# 4G_Modem.net
KiCad netlist of a schematic drawn in Altium Designer
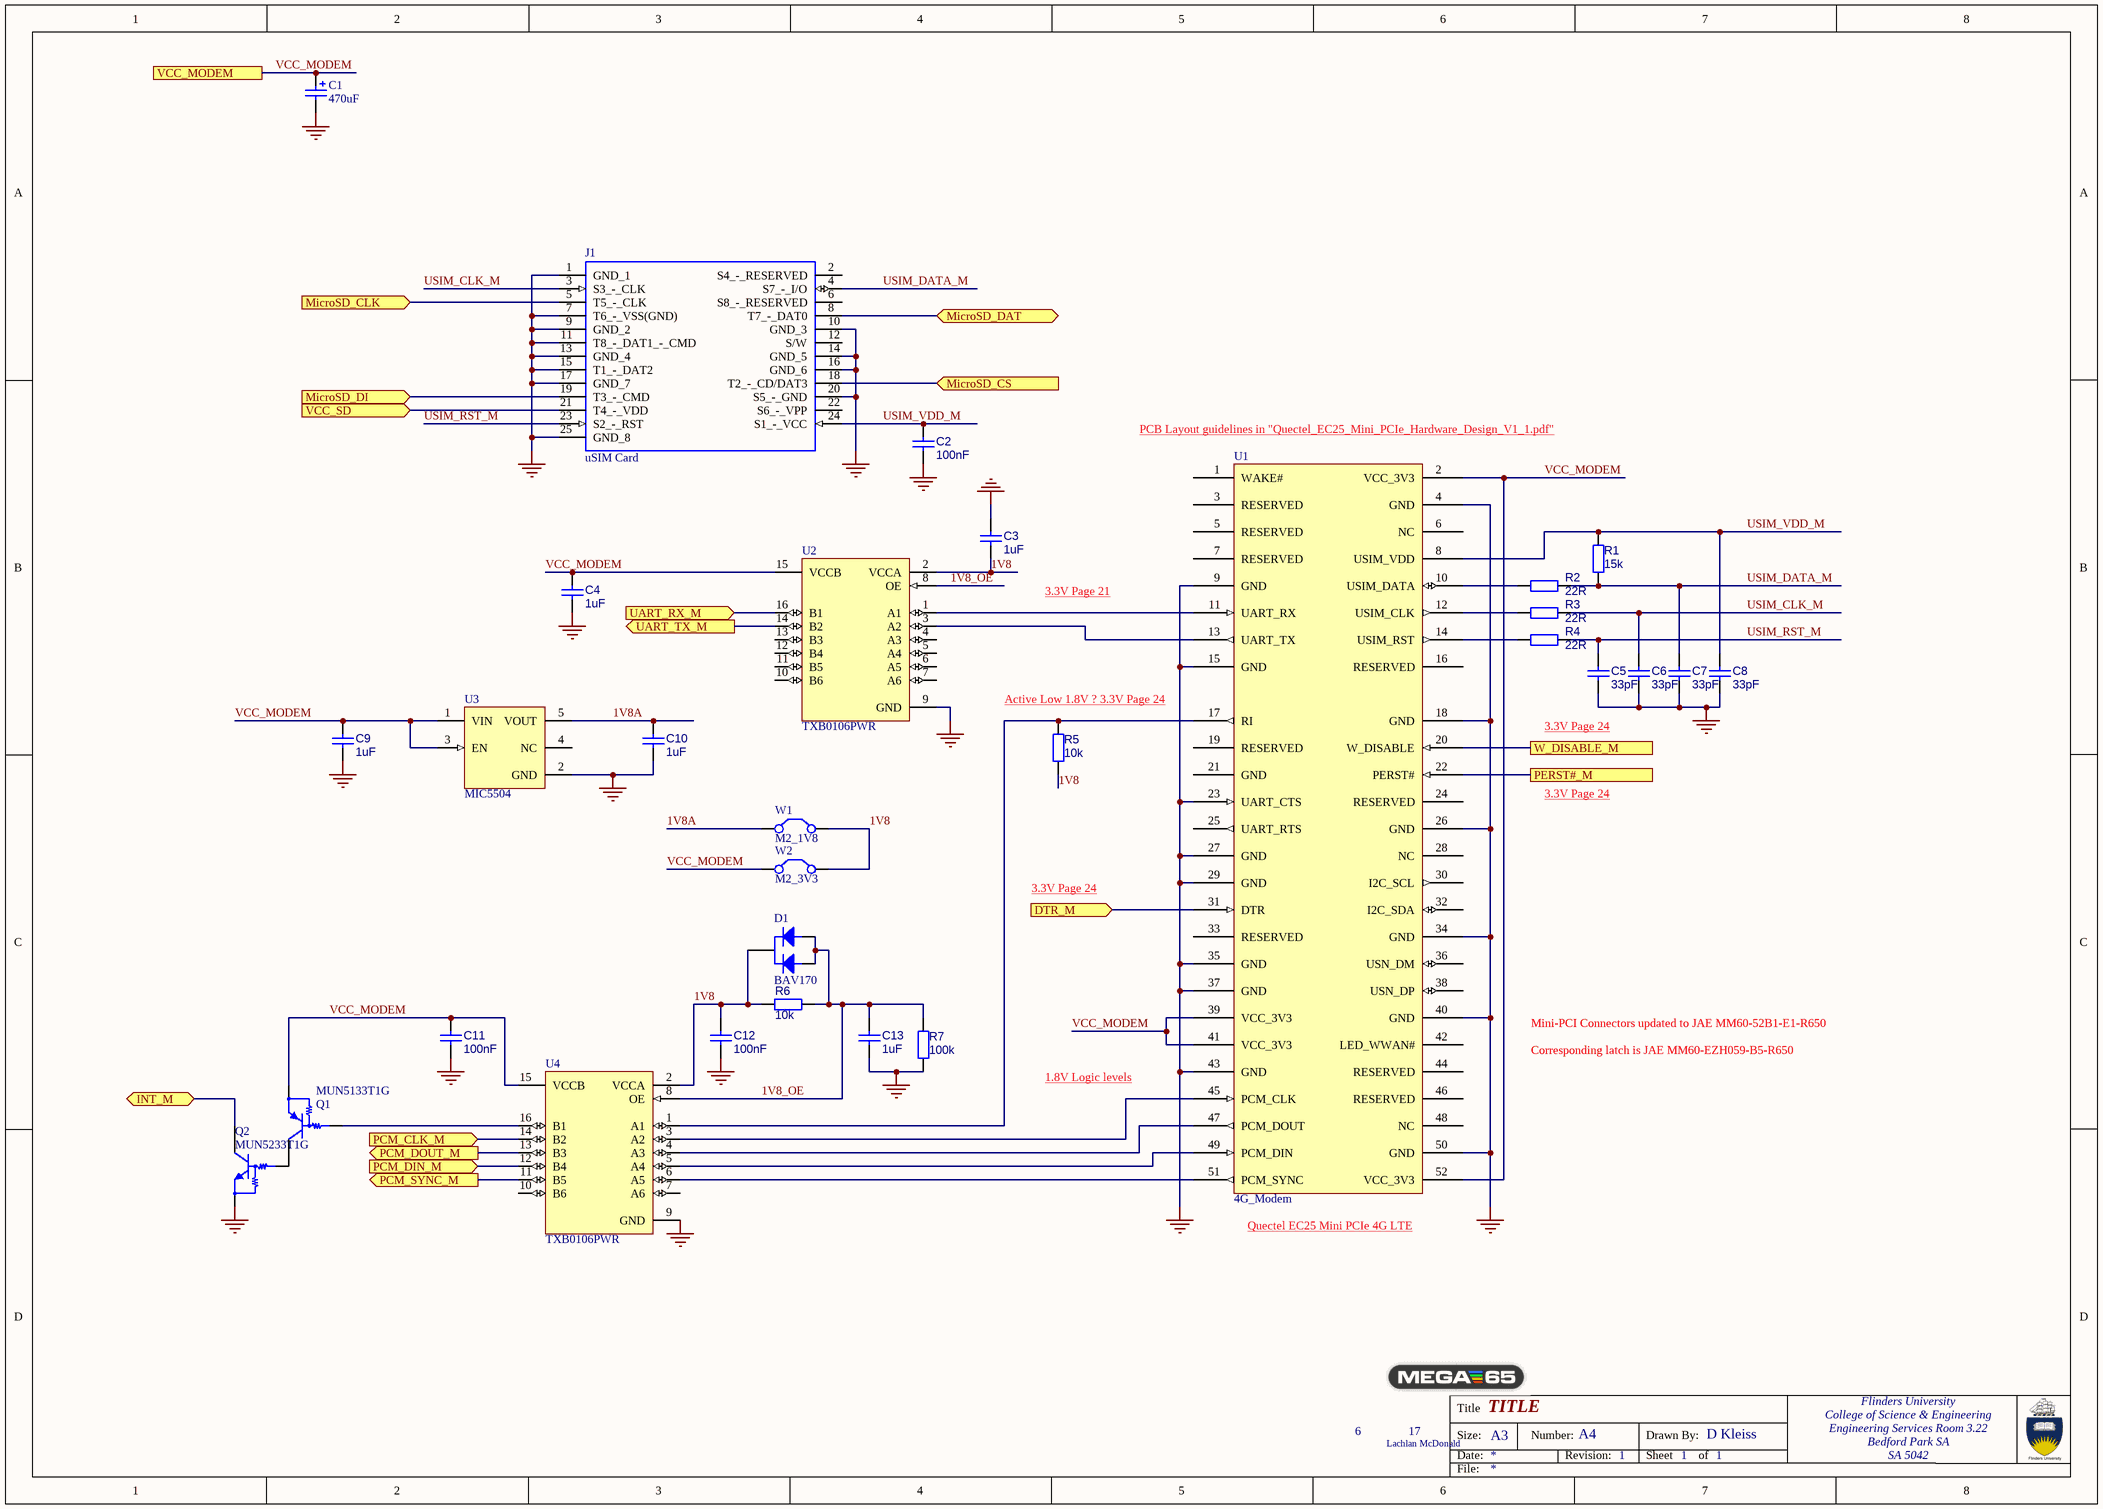
[diagram p0: 4G Modem.SchDoc]

(export (version "E")
  (design (tool "Eeschema 10.0.6"))
  (components
    (comp (ref "C1")
      (value "470uF")
      (footprint "Megaphone:CAP Case D Tantalum")
      (description "Polarized Capacitor (Radial)")
      (fields (field (name "MANUFACTURER") "AVX Corporation"))
      (libsource (lib "Workshop Library 2010_06_24") (part "Cap Pol"))
    )
    (comp (ref "C2")
      (value "100nF")
      (footprint "0603_CAP UF HD")
      (description "Capacitor")
      (libsource (lib "Workshop Library 2010_06_24") (part "Cap"))
    )
    (comp (ref "C3")
      (value "1uF")
      (footprint "0603_CAP UF HD")
      (description "Capacitor")
      (fields (field (name "MANUFACTURER") "Samsung"))
      (libsource (lib "Workshop Library 2010_06_24") (part "Cap"))
    )
    (comp (ref "C4")
      (value "1uF")
      (footprint "0603_CAP UF HD")
      (description "Capacitor")
      (fields (field (name "MANUFACTURER") "Samsung"))
      (libsource (lib "Workshop Library 2010_06_24") (part "Cap"))
    )
    (comp (ref "C5")
      (value "33pF")
      (footprint "0603_CAP PF HD")
      (description "Capacitor")
      (libsource (lib "Workshop Library 2010_06_24") (part "Cap"))
    )
    (comp (ref "C6")
      (value "33pF")
      (footprint "0603_CAP PF HD")
      (description "Capacitor")
      (libsource (lib "Workshop Library 2010_06_24") (part "Cap"))
    )
    (comp (ref "C7")
      (value "33pF")
      (footprint "0603_CAP PF HD")
      (description "Capacitor")
      (libsource (lib "Workshop Library 2010_06_24") (part "Cap"))
    )
    (comp (ref "C8")
      (value "33pF")
      (footprint "0603_CAP PF HD")
      (description "Capacitor")
      (libsource (lib "Workshop Library 2010_06_24") (part "Cap"))
    )
    (comp (ref "C9")
      (value "1uF")
      (footprint "0603_CAP UF HD")
      (description "Capacitor")
      (fields (field (name "MANUFACTURER") "Samsung"))
      (libsource (lib "Workshop Library 2010_06_24") (part "Cap"))
    )
    (comp (ref "C10")
      (value "1uF")
      (footprint "0603_CAP UF HD")
      (description "Capacitor")
      (fields (field (name "MANUFACTURER") "Samsung"))
      (libsource (lib "Workshop Library 2010_06_24") (part "Cap"))
    )
    (comp (ref "C11")
      (value "100nF")
      (footprint "0603_CAP UF HD")
      (description "Capacitor")
      (libsource (lib "Workshop Library 2010_06_24") (part "Cap"))
    )
    (comp (ref "C12")
      (value "100nF")
      (footprint "0603_CAP UF HD")
      (description "Capacitor")
      (libsource (lib "Workshop Library 2010_06_24") (part "Cap"))
    )
    (comp (ref "C13")
      (value "1uF")
      (footprint "0603_CAP UF HD")
      (description "Capacitor")
      (fields (field (name "MANUFACTURER") "Samsung"))
      (libsource (lib "Workshop Library 2010_06_24") (part "Cap"))
    )
    (comp (ref "D1")
      (value "BAV170")
      (footprint "WorkShop_Library_Reflow_Proven 2010_10_27:SOT-23")
      (description "Dual Common Cathode Silicon Low Leakage Diode 3-Pin SOT-23")
      (fields (field (name "MANUFACTURER") "Infineon Technologies"))
      (libsource (lib "Workshop Library 2010_06_24") (part "BAV170"))
    )
    (comp (ref "J1")
      (value "uSIM Card")
      (footprint "CONNECTOR MSIM MOLEX 1046421610")
      (description "Molex 104642 Series 8 Way Micro SIM, MicroSD Memory Card Connector with Solder Termination")
      (fields (field (name "RS PART NUMBER") "1213817P") (field (name "MANUFACTURER") "Molex"))
      (libsource (lib "104642-1610") (part "104642-1610"))
    )
    (comp (ref "Q1")
      (value "MUN5133T1G")
      (footprint "SC70-3 (SOT-323)")
      (description "PNP Bipolar Transistor, Prebiased")
      (fields (field (name "MANUFACTURER") "ON Semiconductor"))
      (libsource (lib "Workshop Library 2010_06_24") (part "Transistor PNP Prebiased"))
    )
    (comp (ref "Q2")
      (value "MUN5233T1G")
      (footprint "SC70-3 (SOT-323)")
      (description "NPN Bipolar Transistor, Prebiased")
      (fields (field (name "MANUFACTURER") "ON Semiconductor"))
      (libsource (lib "Workshop Library 2010_06_24") (part "Transistor NPN Prebiased"))
    )
    (comp (ref "R1")
      (value "15k")
      (footprint "0603-RESISTOR HD")
      (description "Resistor")
      (libsource (lib "Workshop Library 2010_06_24") (part "Resistor"))
    )
    (comp (ref "R2")
      (value "22R")
      (footprint "0603-RESISTOR HD")
      (description "Resistor")
      (libsource (lib "") (part "Resistor_2"))
    )
    (comp (ref "R3")
      (value "22R")
      (footprint "0603-RESISTOR HD")
      (description "Resistor")
      (libsource (lib "") (part "Resistor_2"))
    )
    (comp (ref "R4")
      (value "22R")
      (footprint "0603-RESISTOR HD")
      (description "Resistor")
      (libsource (lib "") (part "Resistor_2"))
    )
    (comp (ref "R5")
      (value "10k")
      (footprint "0603-RESISTOR HD")
      (description "Resistor")
      (libsource (lib "") (part "Resistor_1"))
    )
    (comp (ref "R6")
      (value "10k")
      (footprint "0603-RESISTOR HD")
      (description "Resistor")
      (libsource (lib "") (part "Resistor_3"))
    )
    (comp (ref "R7")
      (value "100k")
      (footprint "0603-RESISTOR HD")
      (description "Resistor")
      (libsource (lib "Workshop Library 2010_06_24") (part "Resistor"))
    )
    (comp (ref "U1")
      (value "4G_Modem")
      (footprint "WorkShop_Library_Unproven 2010_06_18:CONNECTOR MINI PCIE MOLEX_67910001")
      (fields (field (name "MANUFACTURER") "JAE"))
      (libsource (lib "MegaPhone") (part "4G_Modem"))
    )
    (comp (ref "U2")
      (value "TXB0106PWR")
      (footprint "TSSOP-16")
      (fields (field (name "MANUFACTURER") "Texas Instruments"))
      (libsource (lib "Workshop Library 2010_06_24") (part "TXB0106PWR"))
    )
    (comp (ref "U3")
      (value "MIC5504")
      (footprint "SOT-23-5")
      (description "300 mA Single Output LDO in Small Packages")
      (fields (field (name "MANUFACTURER") "Microchip"))
      (libsource (lib "Workshop Library 2010_06_24") (part "MIC5504"))
    )
    (comp (ref "U4")
      (value "TXB0106PWR")
      (footprint "TSSOP-16")
      (fields (field (name "MANUFACTURER") "Texas Instruments"))
      (libsource (lib "Workshop Library 2010_06_24") (part "TXB0106PWR"))
    )
    (comp (ref "W1")
      (value "M2_1V8")
      (footprint "0603-RESISTOR HD")
      (description "Jumper Wire")
      (fields (field (name "PUBLISHER") "Altium Limited"))
      (libsource (lib "Miscellaneous Devices") (part "Jumper"))
    )
    (comp (ref "W2")
      (value "M2_3V3")
      (footprint "0603-RESISTOR HD")
      (description "Jumper Wire")
      (fields (field (name "PUBLISHER") "Altium Limited"))
      (libsource (lib "Miscellaneous Devices") (part "Jumper"))
    )
  )
  (nets
    (net (code "1") (name "/1V8") (class "Default")
      (node (ref "C12") (pin "1") (pinfunction "1_1") (pintype "passive"))
      (node (ref "C3") (pin "1") (pinfunction "1_1") (pintype "passive"))
      (node (ref "D1") (pin "3") (pinfunction "K_3") (pintype "passive"))
      (node (ref "R5") (pin "1") (pinfunction "1_1") (pintype "passive"))
      (node (ref "R6") (pin "1") (pinfunction "1_1") (pintype "passive"))
      (node (ref "U2") (pin "2") (pinfunction "VCCA_2") (pintype "power_in"))
      (node (ref "U4") (pin "2") (pinfunction "VCCA_2") (pintype "power_in"))
      (node (ref "W1") (pin "2") (pinfunction "C2_2") (pintype "passive"))
      (node (ref "W2") (pin "2") (pinfunction "C2_2") (pintype "passive"))
    )
    (net (code "2") (name "/1V8A") (class "Default")
      (node (ref "C10") (pin "1") (pinfunction "1_1") (pintype "passive"))
      (node (ref "U3") (pin "5") (pinfunction "VOUT_5") (pintype "power_in"))
      (node (ref "W1") (pin "1") (pinfunction "C1_1") (pintype "passive"))
    )
    (net (code "3") (name "/1V8_OE") (class "Default")
      (node (ref "C13") (pin "1") (pinfunction "1_1") (pintype "passive"))
      (node (ref "D1") (pin "1") (pinfunction "A1_1") (pintype "passive"))
      (node (ref "D1") (pin "2") (pinfunction "A2_2") (pintype "passive"))
      (node (ref "R6") (pin "2") (pinfunction "2_2") (pintype "passive"))
      (node (ref "R7") (pin "1") (pinfunction "1_1") (pintype "passive"))
      (node (ref "U2") (pin "8") (pinfunction "OE_8") (pintype "input"))
      (node (ref "U4") (pin "8") (pinfunction "OE_8") (pintype "input"))
    )
    (net (code "4") (name "/DTR_M") (class "Default")
      (node (ref "U1") (pin "31") (pinfunction "DTR_31") (pintype "input"))
    )
    (net (code "5") (name "/INT_M") (class "Default")
      (node (ref "Q2") (pin "3") (pinfunction "C_3") (pintype "passive"))
    )
    (net (code "6") (name "/MicroSD_CLK") (class "Default")
      (node (ref "J1") (pin "5") (pinfunction "T5_-_CLK_5") (pintype "passive"))
    )
    (net (code "7") (name "/MicroSD_CS") (class "Default")
      (node (ref "J1") (pin "18") (pinfunction "T2_-_CD/DAT3_18") (pintype "passive"))
    )
    (net (code "8") (name "/MicroSD_DAT") (class "Default")
      (node (ref "J1") (pin "8") (pinfunction "T7_-_DAT0_8") (pintype "passive"))
    )
    (net (code "9") (name "/MicroSD_DI") (class "Default")
      (node (ref "J1") (pin "19") (pinfunction "T3_-_CMD_19") (pintype "passive"))
    )
    (net (code "10") (name "/PCM_CLK_M") (class "Default")
      (node (ref "U4") (pin "14") (pinfunction "B2_14") (pintype "bidirectional"))
    )
    (net (code "11") (name "/PCM_DIN_M") (class "Default")
      (node (ref "U4") (pin "12") (pinfunction "B4_12") (pintype "bidirectional"))
    )
    (net (code "12") (name "/PCM_DOUT_M") (class "Default")
      (node (ref "U4") (pin "13") (pinfunction "B3_13") (pintype "bidirectional"))
    )
    (net (code "13") (name "/PCM_SYNC_M") (class "Default")
      (node (ref "U4") (pin "11") (pinfunction "B5_11") (pintype "bidirectional"))
    )
    (net (code "14") (name "/PERST#_M") (class "Default")
      (node (ref "U1") (pin "22") (pinfunction "PERST#_22") (pintype "input"))
    )
    (net (code "15") (name "/UART_RX_M") (class "Default")
      (node (ref "U2") (pin "16") (pinfunction "B1_16") (pintype "bidirectional"))
    )
    (net (code "16") (name "/UART_TX_M") (class "Default")
      (node (ref "U2") (pin "14") (pinfunction "B2_14") (pintype "bidirectional"))
    )
    (net (code "17") (name "/USIM_CLK_M") (class "Default")
      (node (ref "C6") (pin "1") (pinfunction "1_1") (pintype "passive"))
      (node (ref "J1") (pin "3") (pinfunction "S3_-_CLK_3") (pintype "input"))
      (node (ref "R3") (pin "1") (pinfunction "1_1") (pintype "passive"))
    )
    (net (code "18") (name "/USIM_DATA_M") (class "Default")
      (node (ref "C7") (pin "1") (pinfunction "1_1") (pintype "passive"))
      (node (ref "J1") (pin "4") (pinfunction "S7_-_I/O_4") (pintype "bidirectional"))
      (node (ref "R1") (pin "2") (pinfunction "2_2") (pintype "passive"))
      (node (ref "R2") (pin "1") (pinfunction "1_1") (pintype "passive"))
    )
    (net (code "19") (name "/USIM_RST_M") (class "Default")
      (node (ref "C5") (pin "1") (pinfunction "1_1") (pintype "passive"))
      (node (ref "J1") (pin "23") (pinfunction "S2_-_RST_23") (pintype "input"))
      (node (ref "R4") (pin "1") (pinfunction "1_1") (pintype "passive"))
    )
    (net (code "20") (name "/USIM_VDD_M") (class "Default")
      (node (ref "C2") (pin "1") (pinfunction "1_1") (pintype "passive"))
      (node (ref "C8") (pin "1") (pinfunction "1_1") (pintype "passive"))
      (node (ref "J1") (pin "24") (pinfunction "S1_-_VCC_24") (pintype "input"))
      (node (ref "R1") (pin "1") (pinfunction "1_1") (pintype "passive"))
      (node (ref "U1") (pin "8") (pinfunction "USIM_VDD_8") (pintype "power_in"))
    )
    (net (code "21") (name "/VCC_MODEM") (class "Default")
      (node (ref "C1") (pin "1") (pinfunction "1_1") (pintype "passive"))
      (node (ref "C11") (pin "1") (pinfunction "1_1") (pintype "passive"))
      (node (ref "C4") (pin "1") (pinfunction "1_1") (pintype "passive"))
      (node (ref "C9") (pin "1") (pinfunction "1_1") (pintype "passive"))
      (node (ref "Q1") (pin "2") (pinfunction "E_2") (pintype "passive"))
      (node (ref "U1") (pin "2") (pinfunction "VCC_3V3_2") (pintype "power_in"))
      (node (ref "U1") (pin "39") (pinfunction "VCC_3V3_39") (pintype "power_in"))
      (node (ref "U1") (pin "41") (pinfunction "VCC_3V3_41") (pintype "power_in"))
      (node (ref "U1") (pin "52") (pinfunction "VCC_3V3_52") (pintype "power_in"))
      (node (ref "U2") (pin "15") (pinfunction "VCCB_15") (pintype "power_in"))
      (node (ref "U3") (pin "1") (pinfunction "VIN_1") (pintype "power_in"))
      (node (ref "U3") (pin "3") (pinfunction "EN_3") (pintype "input"))
      (node (ref "U4") (pin "15") (pinfunction "VCCB_15") (pintype "power_in"))
      (node (ref "W2") (pin "1") (pinfunction "C1_1") (pintype "passive"))
    )
    (net (code "22") (name "/VCC_SD") (class "Default")
      (node (ref "J1") (pin "21") (pinfunction "T4_-_VDD_21") (pintype "passive"))
    )
    (net (code "23") (name "/W_DISABLE_M") (class "Default")
      (node (ref "U1") (pin "20") (pinfunction "W_DISABLE_20") (pintype "input"))
    )
    (net (code "24") (name "GND") (class "Default")
      (node (ref "C1") (pin "2") (pinfunction "2_2") (pintype "passive"))
      (node (ref "C10") (pin "2") (pinfunction "2_2") (pintype "passive"))
      (node (ref "C11") (pin "2") (pinfunction "2_2") (pintype "passive"))
      (node (ref "C12") (pin "2") (pinfunction "2_2") (pintype "passive"))
      (node (ref "C13") (pin "2") (pinfunction "2_2") (pintype "passive"))
      (node (ref "C2") (pin "2") (pinfunction "2_2") (pintype "passive"))
      (node (ref "C3") (pin "2") (pinfunction "2_2") (pintype "passive"))
      (node (ref "C4") (pin "2") (pinfunction "2_2") (pintype "passive"))
      (node (ref "C5") (pin "2") (pinfunction "2_2") (pintype "passive"))
      (node (ref "C6") (pin "2") (pinfunction "2_2") (pintype "passive"))
      (node (ref "C7") (pin "2") (pinfunction "2_2") (pintype "passive"))
      (node (ref "C8") (pin "2") (pinfunction "2_2") (pintype "passive"))
      (node (ref "C9") (pin "2") (pinfunction "2_2") (pintype "passive"))
      (node (ref "J1") (pin "1") (pinfunction "GND_1_1") (pintype "passive"))
      (node (ref "J1") (pin "10") (pinfunction "GND_3_10") (pintype "passive"))
      (node (ref "J1") (pin "11") (pinfunction "T8_-_DAT1_-_CMD_11") (pintype "passive"))
      (node (ref "J1") (pin "13") (pinfunction "GND_4_13") (pintype "passive"))
      (node (ref "J1") (pin "14") (pinfunction "GND_5_14") (pintype "passive"))
      (node (ref "J1") (pin "15") (pinfunction "T1_-_DAT2_15") (pintype "passive"))
      (node (ref "J1") (pin "16") (pinfunction "GND_6_16") (pintype "passive"))
      (node (ref "J1") (pin "17") (pinfunction "GND_7_17") (pintype "passive"))
      (node (ref "J1") (pin "20") (pinfunction "S5_-_GND_20") (pintype "passive"))
      (node (ref "J1") (pin "25") (pinfunction "GND_8_25") (pintype "passive"))
      (node (ref "J1") (pin "7") (pinfunction "T6_-_VSS(GND)_7") (pintype "passive"))
      (node (ref "J1") (pin "9") (pinfunction "GND_2_9") (pintype "passive"))
      (node (ref "Q2") (pin "1") (pinfunction "E_1") (pintype "passive"))
      (node (ref "R7") (pin "2") (pinfunction "2_2") (pintype "passive"))
      (node (ref "U1") (pin "15") (pinfunction "GND_15") (pintype "passive"))
      (node (ref "U1") (pin "18") (pinfunction "GND_18") (pintype "passive"))
      (node (ref "U1") (pin "23") (pinfunction "UART_CTS_23") (pintype "input"))
      (node (ref "U1") (pin "26") (pinfunction "GND_26") (pintype "passive"))
      (node (ref "U1") (pin "27") (pinfunction "GND_27") (pintype "passive"))
      (node (ref "U1") (pin "29") (pinfunction "GND_29") (pintype "passive"))
      (node (ref "U1") (pin "34") (pinfunction "GND_34") (pintype "passive"))
      (node (ref "U1") (pin "35") (pinfunction "GND_35") (pintype "passive"))
      (node (ref "U1") (pin "37") (pinfunction "GND_37") (pintype "passive"))
      (node (ref "U1") (pin "4") (pinfunction "GND_4") (pintype "passive"))
      (node (ref "U1") (pin "40") (pinfunction "GND_40") (pintype "passive"))
      (node (ref "U1") (pin "43") (pinfunction "GND_43") (pintype "passive"))
      (node (ref "U1") (pin "50") (pinfunction "GND_50") (pintype "passive"))
      (node (ref "U1") (pin "9") (pinfunction "GND_9") (pintype "passive"))
      (node (ref "U2") (pin "9") (pinfunction "GND_9") (pintype "power_in"))
      (node (ref "U3") (pin "2") (pinfunction "GND_2") (pintype "power_in"))
      (node (ref "U4") (pin "9") (pinfunction "GND_9") (pintype "power_in"))
    )
    (net (code "25") (name "Net-(Q1-B)") (class "Default")
      (node (ref "Q1") (pin "1") (pinfunction "B_1") (pintype "passive"))
      (node (ref "U4") (pin "16") (pinfunction "B1_16") (pintype "bidirectional"))
    )
    (net (code "26") (name "Net-(Q1-C)") (class "Default")
      (node (ref "Q1") (pin "3") (pinfunction "C_3") (pintype "passive"))
      (node (ref "Q2") (pin "2") (pinfunction "B_2") (pintype "passive"))
    )
    (net (code "27") (name "Net-(U1-PCM_CLK)") (class "Default")
      (node (ref "U1") (pin "45") (pinfunction "PCM_CLK_45") (pintype "input"))
      (node (ref "U4") (pin "3") (pinfunction "A2_3") (pintype "bidirectional"))
    )
    (net (code "28") (name "Net-(U1-PCM_DIN)") (class "Default")
      (node (ref "U1") (pin "49") (pinfunction "PCM_DIN_49") (pintype "input"))
      (node (ref "U4") (pin "5") (pinfunction "A4_5") (pintype "bidirectional"))
    )
    (net (code "29") (name "Net-(U1-PCM_DOUT)") (class "Default")
      (node (ref "U1") (pin "47") (pinfunction "PCM_DOUT_47") (pintype "output"))
      (node (ref "U4") (pin "4") (pinfunction "A3_4") (pintype "bidirectional"))
    )
    (net (code "30") (name "Net-(U1-PCM_SYNC)") (class "Default")
      (node (ref "U1") (pin "51") (pinfunction "PCM_SYNC_51") (pintype "output"))
      (node (ref "U4") (pin "6") (pinfunction "A5_6") (pintype "bidirectional"))
    )
    (net (code "31") (name "Net-(U1-RI)") (class "Default")
      (node (ref "R5") (pin "2") (pinfunction "2_2") (pintype "passive"))
      (node (ref "U1") (pin "17") (pinfunction "RI_17") (pintype "output"))
      (node (ref "U4") (pin "1") (pinfunction "A1_1") (pintype "bidirectional"))
    )
    (net (code "32") (name "Net-(U1-UART_RX)") (class "Default")
      (node (ref "U1") (pin "11") (pinfunction "UART_RX_11") (pintype "input"))
      (node (ref "U2") (pin "1") (pinfunction "A1_1") (pintype "bidirectional"))
    )
    (net (code "33") (name "Net-(U1-UART_TX)") (class "Default")
      (node (ref "U1") (pin "13") (pinfunction "UART_TX_13") (pintype "output"))
      (node (ref "U2") (pin "3") (pinfunction "A2_3") (pintype "bidirectional"))
    )
    (net (code "34") (name "Net-(U1-USIM_CLK)") (class "Default")
      (node (ref "R3") (pin "2") (pinfunction "2_2") (pintype "passive"))
      (node (ref "U1") (pin "12") (pinfunction "USIM_CLK_12") (pintype "output"))
    )
    (net (code "35") (name "Net-(U1-USIM_DATA)") (class "Default")
      (node (ref "R2") (pin "2") (pinfunction "2_2") (pintype "passive"))
      (node (ref "U1") (pin "10") (pinfunction "USIM_DATA_10") (pintype "bidirectional"))
    )
    (net (code "36") (name "Net-(U1-USIM_RST)") (class "Default")
      (node (ref "R4") (pin "2") (pinfunction "2_2") (pintype "passive"))
      (node (ref "U1") (pin "14") (pinfunction "USIM_RST_14") (pintype "output"))
    )
    (net (code "37") (name "unconnected-(J1-S4_-_RESERVED-Pad2)") (class "Default")
      (node (ref "J1") (pin "2") (pinfunction "S4_-_RESERVED_2") (pintype "passive"))
    )
    (net (code "38") (name "unconnected-(J1-S6_-_VPP-Pad22)") (class "Default")
      (node (ref "J1") (pin "22") (pinfunction "S6_-_VPP_22") (pintype "passive"))
    )
    (net (code "39") (name "unconnected-(J1-S8_-_RESERVED-Pad6)") (class "Default")
      (node (ref "J1") (pin "6") (pinfunction "S8_-_RESERVED_6") (pintype "passive"))
    )
    (net (code "40") (name "unconnected-(J1-S{slash}W-Pad12)") (class "Default")
      (node (ref "J1") (pin "12") (pinfunction "S/W_12") (pintype "passive"))
    )
    (net (code "41") (name "unconnected-(U1-GND-Pad21)") (class "Default")
      (node (ref "U1") (pin "21") (pinfunction "GND_21") (pintype "passive"))
    )
    (net (code "42") (name "unconnected-(U1-I2C_SCL-Pad30)") (class "Default")
      (node (ref "U1") (pin "30") (pinfunction "I2C_SCL_30") (pintype "output"))
    )
    (net (code "43") (name "unconnected-(U1-I2C_SDA-Pad32)") (class "Default")
      (node (ref "U1") (pin "32") (pinfunction "I2C_SDA_32") (pintype "bidirectional"))
    )
    (net (code "44") (name "unconnected-(U1-LED_WWAN#-Pad42)") (class "Default")
      (node (ref "U1") (pin "42") (pinfunction "LED_WWAN#_42") (pintype "open_collector"))
    )
    (net (code "45") (name "unconnected-(U1-NC-Pad6)") (class "Default")
      (node (ref "U1") (pin "6") (pinfunction "NC_6") (pintype "passive"))
    )
    (net (code "46") (name "unconnected-(U1-NC-Pad28)") (class "Default")
      (node (ref "U1") (pin "28") (pinfunction "NC_28") (pintype "passive"))
    )
    (net (code "47") (name "unconnected-(U1-NC-Pad48)") (class "Default")
      (node (ref "U1") (pin "48") (pinfunction "NC_48") (pintype "passive"))
    )
    (net (code "48") (name "unconnected-(U1-RESERVED-Pad3)") (class "Default")
      (node (ref "U1") (pin "3") (pinfunction "RESERVED_3") (pintype "passive"))
    )
    (net (code "49") (name "unconnected-(U1-RESERVED-Pad5)") (class "Default")
      (node (ref "U1") (pin "5") (pinfunction "RESERVED_5") (pintype "passive"))
    )
    (net (code "50") (name "unconnected-(U1-RESERVED-Pad7)") (class "Default")
      (node (ref "U1") (pin "7") (pinfunction "RESERVED_7") (pintype "passive"))
    )
    (net (code "51") (name "unconnected-(U1-RESERVED-Pad16)") (class "Default")
      (node (ref "U1") (pin "16") (pinfunction "RESERVED_16") (pintype "passive"))
    )
    (net (code "52") (name "unconnected-(U1-RESERVED-Pad19)") (class "Default")
      (node (ref "U1") (pin "19") (pinfunction "RESERVED_19") (pintype "passive"))
    )
    (net (code "53") (name "unconnected-(U1-RESERVED-Pad24)") (class "Default")
      (node (ref "U1") (pin "24") (pinfunction "RESERVED_24") (pintype "passive"))
    )
    (net (code "54") (name "unconnected-(U1-RESERVED-Pad33)") (class "Default")
      (node (ref "U1") (pin "33") (pinfunction "RESERVED_33") (pintype "passive"))
    )
    (net (code "55") (name "unconnected-(U1-RESERVED-Pad44)") (class "Default")
      (node (ref "U1") (pin "44") (pinfunction "RESERVED_44") (pintype "passive"))
    )
    (net (code "56") (name "unconnected-(U1-RESERVED-Pad46)") (class "Default")
      (node (ref "U1") (pin "46") (pinfunction "RESERVED_46") (pintype "passive"))
    )
    (net (code "57") (name "unconnected-(U1-UART_RTS-Pad25)") (class "Default")
      (node (ref "U1") (pin "25") (pinfunction "UART_RTS_25") (pintype "output"))
    )
    (net (code "58") (name "unconnected-(U1-USN_DM-Pad36)") (class "Default")
      (node (ref "U1") (pin "36") (pinfunction "USN_DM_36") (pintype "bidirectional"))
    )
    (net (code "59") (name "unconnected-(U1-USN_DP-Pad38)") (class "Default")
      (node (ref "U1") (pin "38") (pinfunction "USN_DP_38") (pintype "bidirectional"))
    )
    (net (code "60") (name "unconnected-(U1-WAKE#-Pad1)") (class "Default")
      (node (ref "U1") (pin "1") (pinfunction "WAKE#_1") (pintype "open_collector"))
    )
    (net (code "61") (name "unconnected-(U2-A3-Pad4)") (class "Default")
      (node (ref "U2") (pin "4") (pinfunction "A3_4") (pintype "bidirectional"))
    )
    (net (code "62") (name "unconnected-(U2-A4-Pad5)") (class "Default")
      (node (ref "U2") (pin "5") (pinfunction "A4_5") (pintype "bidirectional"))
    )
    (net (code "63") (name "unconnected-(U2-A5-Pad6)") (class "Default")
      (node (ref "U2") (pin "6") (pinfunction "A5_6") (pintype "bidirectional"))
    )
    (net (code "64") (name "unconnected-(U2-A6-Pad7)") (class "Default")
      (node (ref "U2") (pin "7") (pinfunction "A6_7") (pintype "bidirectional"))
    )
    (net (code "65") (name "unconnected-(U2-B3-Pad13)") (class "Default")
      (node (ref "U2") (pin "13") (pinfunction "B3_13") (pintype "bidirectional"))
    )
    (net (code "66") (name "unconnected-(U2-B4-Pad12)") (class "Default")
      (node (ref "U2") (pin "12") (pinfunction "B4_12") (pintype "bidirectional"))
    )
    (net (code "67") (name "unconnected-(U2-B5-Pad11)") (class "Default")
      (node (ref "U2") (pin "11") (pinfunction "B5_11") (pintype "bidirectional"))
    )
    (net (code "68") (name "unconnected-(U2-B6-Pad10)") (class "Default")
      (node (ref "U2") (pin "10") (pinfunction "B6_10") (pintype "bidirectional"))
    )
    (net (code "69") (name "unconnected-(U3-NC-Pad4)") (class "Default")
      (node (ref "U3") (pin "4") (pinfunction "NC_4") (pintype "passive"))
    )
    (net (code "70") (name "unconnected-(U4-A6-Pad7)") (class "Default")
      (node (ref "U4") (pin "7") (pinfunction "A6_7") (pintype "bidirectional"))
    )
    (net (code "71") (name "unconnected-(U4-B6-Pad10)") (class "Default")
      (node (ref "U4") (pin "10") (pinfunction "B6_10") (pintype "bidirectional"))
    )
  )
)
